# Controller.net
KiCad netlist of a schematic drawn in EAGLE
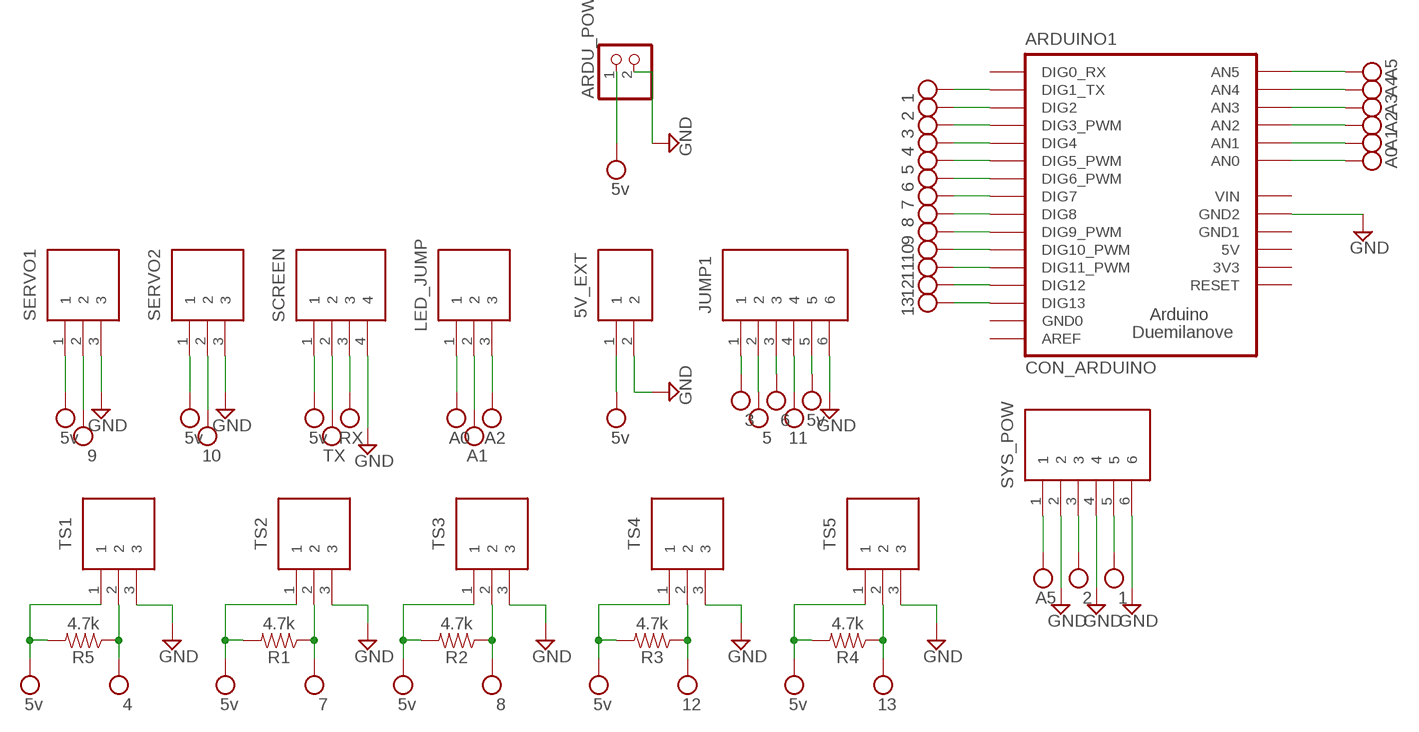
[diagram p0: schematic, sheet 1]

(export (version "E")
  (design (tool "Eeschema 10.0.6"))
  (components
    (comp (ref "5V_EXT")
      (value "S2B-XH-A(LF)(SN)")
      (footprint "eagle-import:SHDR2W80P0X250_1X2_740X575X700")
      (fields (field (name "RS_PART_NUMBER") "8201582"))
      (libsource (lib "eagle-import") (part "S2B-XH-A(LF)(SN)"))
    )
    (comp (ref "ARDUINO1")
      (value "CON_ARDUINO")
      (footprint "eagle-import:CON_ARDUINO")
      (libsource (lib "eagle-import") (part "CON_ARDUINO"))
    )
    (comp (ref "ARDU_POW")
      (value "PINHD-1X2")
      (footprint "eagle-import:1X02")
      (libsource (lib "eagle-import") (part "PINHD-1X2"))
    )
    (comp (ref "JUMP1")
      (value "S6B-XH-A(LF)(SN)")
      (footprint "eagle-import:SHDR6W64P0X250_1X6_1740X1155X7")
      (fields (field (name "RS_PART_NUMBER") "8201591"))
      (libsource (lib "eagle-import") (part "S6B-XH-A(LF)(SN)"))
    )
    (comp (ref "LED_JUMP")
      (value "S3B-XH-A(LF)(SN)")
      (footprint "eagle-import:SHDR3W80P0X250_1X3_990X610X700")
      (fields (field (name "RS_PART_NUMBER") "8201585"))
      (libsource (lib "eagle-import") (part "S3B-XH-A(LF)(SN)"))
    )
    (comp (ref "R1")
      (value "4.7k")
      (footprint "eagle-import:AXIAL-0.3")
      (libsource (lib "eagle-import") (part "10KOHM-HORIZ-1/4W-5%"))
    )
    (comp (ref "R2")
      (value "4.7k")
      (footprint "eagle-import:AXIAL-0.3")
      (libsource (lib "eagle-import") (part "10KOHM-HORIZ-1/4W-5%"))
    )
    (comp (ref "R3")
      (value "4.7k")
      (footprint "eagle-import:AXIAL-0.3")
      (libsource (lib "eagle-import") (part "10KOHM-HORIZ-1/4W-5%"))
    )
    (comp (ref "R4")
      (value "4.7k")
      (footprint "eagle-import:AXIAL-0.3")
      (libsource (lib "eagle-import") (part "10KOHM-HORIZ-1/4W-5%"))
    )
    (comp (ref "R5")
      (value "4.7k")
      (footprint "eagle-import:AXIAL-0.3")
      (libsource (lib "eagle-import") (part "10KOHM-HORIZ-1/4W-5%"))
    )
    (comp (ref "SCREEN")
      (value "S4B-XH-A(LF)(SN)")
      (footprint "eagle-import:SHDR4W64P0X250_1X4_1240X1155X7")
      (fields (field (name "RS_PART_NUMBER") "8201589"))
      (libsource (lib "eagle-import") (part "S4B-XH-A(LF)(SN)"))
    )
    (comp (ref "SERVO1")
      (value "S3B-XH-A(LF)(SN)")
      (footprint "eagle-import:SHDR3W80P0X250_1X3_990X610X700")
      (fields (field (name "RS_PART_NUMBER") "8201585"))
      (libsource (lib "eagle-import") (part "S3B-XH-A(LF)(SN)"))
    )
    (comp (ref "SERVO2")
      (value "S3B-XH-A(LF)(SN)")
      (footprint "eagle-import:SHDR3W80P0X250_1X3_990X610X700")
      (fields (field (name "RS_PART_NUMBER") "8201585"))
      (libsource (lib "eagle-import") (part "S3B-XH-A(LF)(SN)"))
    )
    (comp (ref "SYS_POW")
      (value "S6B-XH-A(LF)(SN)")
      (footprint "eagle-import:SHDR6W64P0X250_1X6_1740X1155X7")
      (fields (field (name "RS_PART_NUMBER") "8201591"))
      (libsource (lib "eagle-import") (part "S6B-XH-A(LF)(SN)"))
    )
    (comp (ref "TS1")
      (value "S3B-XH-A(LF)(SN)")
      (footprint "eagle-import:SHDR3W80P0X250_1X3_990X610X700")
      (fields (field (name "RS_PART_NUMBER") "8201585"))
      (libsource (lib "eagle-import") (part "S3B-XH-A(LF)(SN)"))
    )
    (comp (ref "TS2")
      (value "S3B-XH-A(LF)(SN)")
      (footprint "eagle-import:SHDR3W80P0X250_1X3_990X610X700")
      (fields (field (name "RS_PART_NUMBER") "8201585"))
      (libsource (lib "eagle-import") (part "S3B-XH-A(LF)(SN)"))
    )
    (comp (ref "TS3")
      (value "S3B-XH-A(LF)(SN)")
      (footprint "eagle-import:SHDR3W80P0X250_1X3_990X610X700")
      (fields (field (name "RS_PART_NUMBER") "8201585"))
      (libsource (lib "eagle-import") (part "S3B-XH-A(LF)(SN)"))
    )
    (comp (ref "TS4")
      (value "S3B-XH-A(LF)(SN)")
      (footprint "eagle-import:SHDR3W80P0X250_1X3_990X610X700")
      (fields (field (name "RS_PART_NUMBER") "8201585"))
      (libsource (lib "eagle-import") (part "S3B-XH-A(LF)(SN)"))
    )
    (comp (ref "TS5")
      (value "S3B-XH-A(LF)(SN)")
      (footprint "eagle-import:SHDR3W80P0X250_1X3_990X610X700")
      (fields (field (name "RS_PART_NUMBER") "8201585"))
      (libsource (lib "eagle-import") (part "S3B-XH-A(LF)(SN)"))
    )
  )
  (nets
    (net (code "1") (name "/GND0") (class "Default")
      (node (ref "ARDUINO1") (pin "GND0") (pinfunction "GND0_GND0") (pintype "power_in"))
    )
    (net (code "2") (name "/GND1") (class "Default")
      (node (ref "ARDUINO1") (pin "GND1") (pinfunction "GND1_GND1") (pintype "power_in"))
    )
    (net (code "3") (name "/VIN") (class "Default")
      (node (ref "ARDUINO1") (pin "VIN") (pinfunction "VIN_VIN") (pintype "power_in"))
    )
    (net (code "4") (name "1") (class "Default")
      (node (ref "ARDUINO1") (pin "D_1") (pinfunction "DIG1_TX_D_1") (pintype "bidirectional"))
      (node (ref "SYS_POW") (pin "5") (pinfunction "5_5") (pintype "passive"))
    )
    (net (code "5") (name "2") (class "Default")
      (node (ref "ARDUINO1") (pin "D_2") (pinfunction "DIG2_D_2") (pintype "bidirectional"))
      (node (ref "SYS_POW") (pin "3") (pinfunction "3_3") (pintype "passive"))
    )
    (net (code "6") (name "3") (class "Default")
      (node (ref "ARDUINO1") (pin "D_3") (pinfunction "DIG3_PWM_D_3") (pintype "bidirectional"))
      (node (ref "JUMP1") (pin "1") (pinfunction "1_1") (pintype "passive"))
    )
    (net (code "7") (name "4") (class "Default")
      (node (ref "ARDUINO1") (pin "D_4") (pinfunction "DIG4_D_4") (pintype "bidirectional"))
      (node (ref "R5") (pin "P$1") (pinfunction "1_P$1") (pintype "passive"))
      (node (ref "TS1") (pin "2") (pinfunction "2_2") (pintype "passive"))
    )
    (net (code "8") (name "5") (class "Default")
      (node (ref "ARDUINO1") (pin "D_5") (pinfunction "DIG5_PWM_D_5") (pintype "bidirectional"))
      (node (ref "JUMP1") (pin "2") (pinfunction "2_2") (pintype "passive"))
    )
    (net (code "9") (name "5v") (class "Default")
      (node (ref "5V_EXT") (pin "1") (pinfunction "1_1") (pintype "passive"))
      (node (ref "ARDU_POW") (pin "1") (pinfunction "1_1") (pintype "passive"))
      (node (ref "JUMP1") (pin "5") (pinfunction "5_5") (pintype "passive"))
      (node (ref "R1") (pin "P$2") (pinfunction "2_P$2") (pintype "passive"))
      (node (ref "R2") (pin "P$2") (pinfunction "2_P$2") (pintype "passive"))
      (node (ref "R3") (pin "P$2") (pinfunction "2_P$2") (pintype "passive"))
      (node (ref "R4") (pin "P$2") (pinfunction "2_P$2") (pintype "passive"))
      (node (ref "R5") (pin "P$2") (pinfunction "2_P$2") (pintype "passive"))
      (node (ref "SCREEN") (pin "1") (pinfunction "1_1") (pintype "passive"))
      (node (ref "SERVO1") (pin "1") (pinfunction "1_1") (pintype "passive"))
      (node (ref "SERVO2") (pin "1") (pinfunction "1_1") (pintype "passive"))
      (node (ref "TS1") (pin "1") (pinfunction "1_1") (pintype "passive"))
      (node (ref "TS2") (pin "1") (pinfunction "1_1") (pintype "passive"))
      (node (ref "TS3") (pin "1") (pinfunction "1_1") (pintype "passive"))
      (node (ref "TS4") (pin "1") (pinfunction "1_1") (pintype "passive"))
      (node (ref "TS5") (pin "1") (pinfunction "1_1") (pintype "passive"))
    )
    (net (code "10") (name "6") (class "Default")
      (node (ref "ARDUINO1") (pin "D_6") (pinfunction "DIG6_PWM_D_6") (pintype "bidirectional"))
      (node (ref "JUMP1") (pin "3") (pinfunction "3_3") (pintype "passive"))
    )
    (net (code "11") (name "7") (class "Default")
      (node (ref "ARDUINO1") (pin "D_7") (pinfunction "DIG7_D_7") (pintype "bidirectional"))
      (node (ref "R1") (pin "P$1") (pinfunction "1_P$1") (pintype "passive"))
      (node (ref "TS2") (pin "2") (pinfunction "2_2") (pintype "passive"))
    )
    (net (code "12") (name "8") (class "Default")
      (node (ref "ARDUINO1") (pin "D_8") (pinfunction "DIG8_D_8") (pintype "bidirectional"))
      (node (ref "R2") (pin "P$1") (pinfunction "1_P$1") (pintype "passive"))
      (node (ref "TS3") (pin "2") (pinfunction "2_2") (pintype "passive"))
    )
    (net (code "13") (name "9") (class "Default")
      (node (ref "ARDUINO1") (pin "D_9") (pinfunction "DIG9_PWM_D_9") (pintype "bidirectional"))
      (node (ref "SERVO1") (pin "2") (pinfunction "2_2") (pintype "passive"))
    )
    (net (code "14") (name "10") (class "Default")
      (node (ref "ARDUINO1") (pin "D_10") (pinfunction "DIG10_PWM_D_10") (pintype "bidirectional"))
      (node (ref "SERVO2") (pin "2") (pinfunction "2_2") (pintype "passive"))
    )
    (net (code "15") (name "11") (class "Default")
      (node (ref "ARDUINO1") (pin "D_11") (pinfunction "DIG11_PWM_D_11") (pintype "bidirectional"))
      (node (ref "JUMP1") (pin "4") (pinfunction "4_4") (pintype "passive"))
    )
    (net (code "16") (name "12") (class "Default")
      (node (ref "ARDUINO1") (pin "D_12") (pinfunction "DIG12_D_12") (pintype "bidirectional"))
      (node (ref "R3") (pin "P$1") (pinfunction "1_P$1") (pintype "passive"))
      (node (ref "TS4") (pin "2") (pinfunction "2_2") (pintype "passive"))
    )
    (net (code "17") (name "13") (class "Default")
      (node (ref "ARDUINO1") (pin "D_13") (pinfunction "DIG13_D_13") (pintype "bidirectional"))
      (node (ref "R4") (pin "P$1") (pinfunction "1_P$1") (pintype "passive"))
      (node (ref "TS5") (pin "2") (pinfunction "2_2") (pintype "passive"))
    )
    (net (code "18") (name "A0") (class "Default")
      (node (ref "ARDUINO1") (pin "A_0") (pinfunction "AN0_A_0") (pintype "input"))
      (node (ref "LED_JUMP") (pin "1") (pinfunction "1_1") (pintype "passive"))
    )
    (net (code "19") (name "A1") (class "Default")
      (node (ref "ARDUINO1") (pin "A_1") (pinfunction "AN1_A_1") (pintype "input"))
      (node (ref "LED_JUMP") (pin "2") (pinfunction "2_2") (pintype "passive"))
    )
    (net (code "20") (name "A2") (class "Default")
      (node (ref "ARDUINO1") (pin "A_2") (pinfunction "AN2_A_2") (pintype "input"))
      (node (ref "LED_JUMP") (pin "3") (pinfunction "3_3") (pintype "passive"))
    )
    (net (code "21") (name "A3") (class "Default")
      (node (ref "ARDUINO1") (pin "A_3") (pinfunction "AN3_A_3") (pintype "input"))
      (node (ref "SCREEN") (pin "2") (pinfunction "2_2") (pintype "passive"))
    )
    (net (code "22") (name "A4") (class "Default")
      (node (ref "ARDUINO1") (pin "A_4") (pinfunction "AN4_A_4") (pintype "input"))
      (node (ref "SCREEN") (pin "3") (pinfunction "3_3") (pintype "passive"))
    )
    (net (code "23") (name "A5") (class "Default")
      (node (ref "ARDUINO1") (pin "A_5") (pinfunction "AN5_A_5") (pintype "input"))
      (node (ref "SYS_POW") (pin "1") (pinfunction "1_1") (pintype "passive"))
    )
    (net (code "24") (name "GND") (class "Default")
      (node (ref "5V_EXT") (pin "2") (pinfunction "2_2") (pintype "passive"))
      (node (ref "ARDUINO1") (pin "GND2") (pinfunction "GND2_GND2") (pintype "power_in"))
      (node (ref "ARDU_POW") (pin "2") (pinfunction "2_2") (pintype "passive"))
      (node (ref "JUMP1") (pin "6") (pinfunction "6_6") (pintype "passive"))
      (node (ref "SCREEN") (pin "4") (pinfunction "4_4") (pintype "passive"))
      (node (ref "SERVO1") (pin "3") (pinfunction "3_3") (pintype "passive"))
      (node (ref "SERVO2") (pin "3") (pinfunction "3_3") (pintype "passive"))
      (node (ref "SYS_POW") (pin "2") (pinfunction "2_2") (pintype "passive"))
      (node (ref "SYS_POW") (pin "4") (pinfunction "4_4") (pintype "passive"))
      (node (ref "SYS_POW") (pin "6") (pinfunction "6_6") (pintype "passive"))
      (node (ref "TS1") (pin "3") (pinfunction "3_3") (pintype "passive"))
      (node (ref "TS2") (pin "3") (pinfunction "3_3") (pintype "passive"))
      (node (ref "TS3") (pin "3") (pinfunction "3_3") (pintype "passive"))
      (node (ref "TS4") (pin "3") (pinfunction "3_3") (pintype "passive"))
      (node (ref "TS5") (pin "3") (pinfunction "3_3") (pintype "passive"))
    )
    (net (code "25") (name "unconnected-(ARDUINO1-DIG0_RX-PadD_0)") (class "Default")
      (node (ref "ARDUINO1") (pin "D_0") (pinfunction "DIG0_RX_D_0") (pintype "bidirectional"))
    )
    (net (code "26") (name "unconnected-(ARDUINO1-Pad3V3)") (class "Default")
      (node (ref "ARDUINO1") (pin "3V3") (pinfunction "3V3_3V3") (pintype "bidirectional"))
    )
    (net (code "27") (name "unconnected-(ARDUINO1-Pad5V)") (class "Default")
      (node (ref "ARDUINO1") (pin "5V") (pinfunction "5V_5V") (pintype "bidirectional"))
    )
    (net (code "28") (name "unconnected-(ARDUINO1-PadAREF)") (class "Default")
      (node (ref "ARDUINO1") (pin "AREF") (pinfunction "AREF_AREF") (pintype "bidirectional"))
    )
    (net (code "29") (name "unconnected-(ARDUINO1-PadRESET)") (class "Default")
      (node (ref "ARDUINO1") (pin "RESET") (pinfunction "RESET_RESET") (pintype "input"))
    )
  )
)
